# 8_PCIE-WIFI.net
KiCad netlist of a schematic drawn in Altium Designer
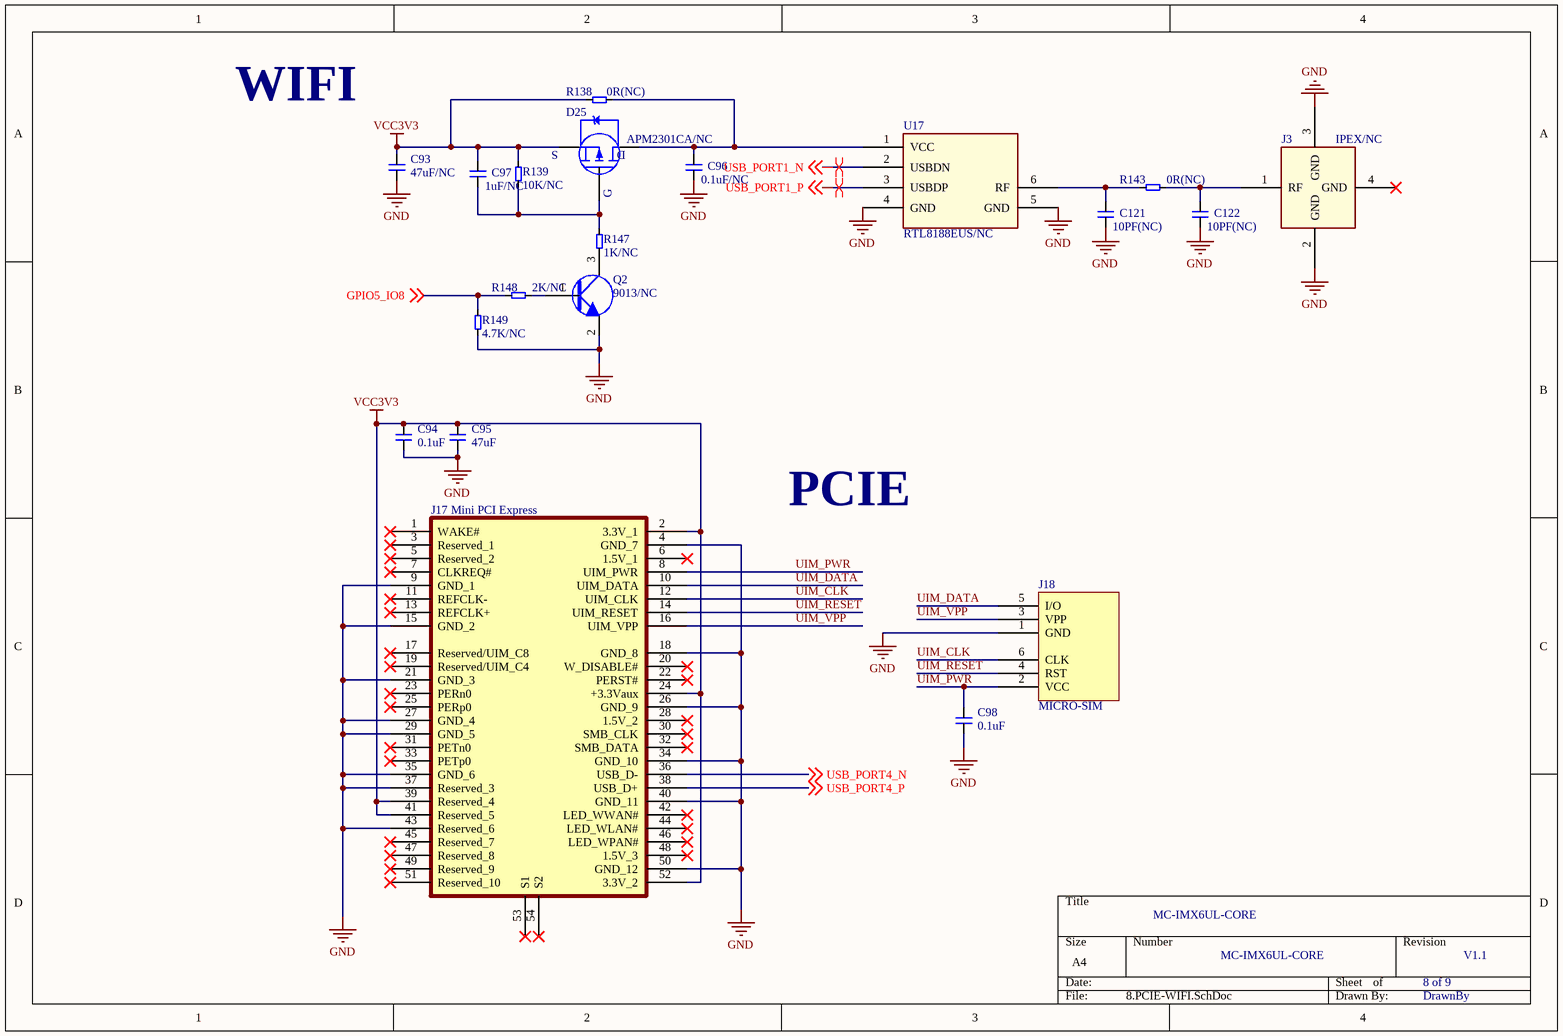
[diagram p0: 8.PCIE-WIFI.SchDoc]

(export (version "E")
  (design (tool "Eeschema 10.0.6"))
  (components
    (comp (ref "C93")
      (value "47uF/NC")
      (footprint "1206C")
      (description "电容")
      (libsource (lib "LDT-SCH") (part "电容"))
    )
    (comp (ref "C94")
      (value "0.1uF")
      (footprint "0603C")
      (description "电容")
      (libsource (lib "LDT-SCH") (part "电容"))
    )
    (comp (ref "C95")
      (value "47uF")
      (footprint "1206C")
      (description "电容")
      (libsource (lib "LDT-SCH") (part "电容"))
    )
    (comp (ref "C96")
      (value "0.1uF/NC")
      (footprint "0603C")
      (description "电容")
      (libsource (lib "LDT-SCH") (part "电容"))
    )
    (comp (ref "C97")
      (value "1uF/NC")
      (footprint "0603C")
      (description "电容")
      (libsource (lib "LDT-SCH") (part "电容"))
    )
    (comp (ref "C98")
      (value "0.1uF")
      (footprint "0603C")
      (description "电容")
      (libsource (lib "LDT-SCH") (part "电容"))
    )
    (comp (ref "C121")
      (value "10PF(NC)")
      (footprint "0402C")
      (description "电容")
      (libsource (lib "LDT-SCH") (part "电容"))
    )
    (comp (ref "C122")
      (value "10PF(NC)")
      (footprint "0402C")
      (description "电容")
      (libsource (lib "LDT-SCH") (part "电容"))
    )
    (comp (ref "D25")
      (value "APM2301CA/NC")
      (footprint "SOT-23")
      (libsource (lib "LDT-SCH") (part "APM2301CA"))
    )
    (comp (ref "J3") (value "IPEX/NC") (footprint "IPEX") (libsource (lib "LDT-SCH") (part "IPEX")))
    (comp (ref "J17")
      (value "Mini PCI Express")
      (footprint "MINI-PCIE")
      (description "MPC24-52K3311")
      (libsource (lib "LDT-SCH") (part "MINIPCIE"))
    )
    (comp (ref "J18")
      (value "MICRO-SIM")
      (footprint "MACRO-SIM")
      (libsource (lib "LDT-SCH") (part "MICRO-SIM"))
    )
    (comp (ref "Q2") (value "9013/NC") (footprint "SOT-23") (libsource (lib "LDT-SCH") (part "9013")))
    (comp (ref "R138")
      (value "0R(NC)")
      (footprint "0603R")
      (description "电阻")
      (libsource (lib "*") (part "电阻"))
    )
    (comp (ref "R139")
      (value "10K/NC")
      (footprint "0603R")
      (description "电阻")
      (libsource (lib "*") (part "电阻"))
    )
    (comp (ref "R143")
      (value "0R(NC)")
      (footprint "0402R")
      (description "电阻")
      (libsource (lib "*") (part "电阻"))
    )
    (comp (ref "R147")
      (value "1K/NC")
      (footprint "0603R")
      (description "电阻")
      (libsource (lib "*") (part "电阻"))
    )
    (comp (ref "R148")
      (value "2K/NC")
      (footprint "0603R")
      (description "电阻")
      (libsource (lib "*") (part "电阻"))
    )
    (comp (ref "R149")
      (value "4.7K/NC")
      (footprint "0603R")
      (description "电阻")
      (libsource (lib "*") (part "电阻"))
    )
    (comp (ref "U17")
      (value "RTL8188EUS/NC")
      (footprint "RTL8188EUS 13*12.2")
      (libsource (lib "LDT-SCH") (part "RTL8188EUS-13*12.2"))
    )
  )
  (nets
    (net (code "1") (name "/UIM_CLK") (class "Default")
      (node (ref "J17") (pin "12") (pinfunction "UIM_CLK_12") (pintype "passive"))
      (node (ref "J18") (pin "6") (pinfunction "CLK_6") (pintype "passive"))
    )
    (net (code "2") (name "/UIM_DATA") (class "Default")
      (node (ref "J17") (pin "10") (pinfunction "UIM_DATA_10") (pintype "passive"))
      (node (ref "J18") (pin "5") (pinfunction "I/O_5") (pintype "passive"))
    )
    (net (code "3") (name "/UIM_PWR") (class "Default")
      (node (ref "C98") (pin "1") (pintype "passive"))
      (node (ref "J17") (pin "8") (pinfunction "UIM_PWR_8") (pintype "passive"))
      (node (ref "J18") (pin "2") (pinfunction "VCC_2") (pintype "passive"))
    )
    (net (code "4") (name "/UIM_RESET") (class "Default")
      (node (ref "J17") (pin "14") (pinfunction "UIM_RESET_14") (pintype "passive"))
      (node (ref "J18") (pin "4") (pinfunction "RST_4") (pintype "passive"))
    )
    (net (code "5") (name "/UIM_VPP") (class "Default")
      (node (ref "J17") (pin "16") (pinfunction "UIM_VPP_16") (pintype "passive"))
      (node (ref "J18") (pin "3") (pinfunction "VPP_3") (pintype "passive"))
    )
    (net (code "6") (name "GND") (class "Default")
      (node (ref "C121") (pin "2") (pintype "passive"))
      (node (ref "C122") (pin "2") (pintype "passive"))
      (node (ref "C93") (pin "2") (pintype "passive"))
      (node (ref "C94") (pin "2") (pintype "passive"))
      (node (ref "C95") (pin "2") (pintype "passive"))
      (node (ref "C96") (pin "2") (pintype "passive"))
      (node (ref "C98") (pin "2") (pintype "passive"))
      (node (ref "J17") (pin "15") (pinfunction "GND_2_15") (pintype "passive"))
      (node (ref "J17") (pin "18") (pinfunction "GND_8_18") (pintype "passive"))
      (node (ref "J17") (pin "21") (pinfunction "GND_3_21") (pintype "passive"))
      (node (ref "J17") (pin "26") (pinfunction "GND_9_26") (pintype "passive"))
      (node (ref "J17") (pin "27") (pinfunction "GND_4_27") (pintype "passive"))
      (node (ref "J17") (pin "29") (pinfunction "GND_5_29") (pintype "passive"))
      (node (ref "J17") (pin "34") (pinfunction "GND_10_34") (pintype "passive"))
      (node (ref "J17") (pin "35") (pinfunction "GND_6_35") (pintype "passive"))
      (node (ref "J17") (pin "37") (pinfunction "Reserved_3_37") (pintype "passive"))
      (node (ref "J17") (pin "4") (pinfunction "GND_7_4") (pintype "passive"))
      (node (ref "J17") (pin "40") (pinfunction "GND_11_40") (pintype "passive"))
      (node (ref "J17") (pin "43") (pinfunction "Reserved_6_43") (pintype "passive"))
      (node (ref "J17") (pin "50") (pinfunction "GND_12_50") (pintype "passive"))
      (node (ref "J17") (pin "9") (pinfunction "GND_1_9") (pintype "passive"))
      (node (ref "J18") (pin "1") (pinfunction "GND_1") (pintype "passive"))
      (node (ref "J3") (pin "2") (pinfunction "GND_2") (pintype "passive"))
      (node (ref "J3") (pin "3") (pinfunction "GND_3") (pintype "passive"))
      (node (ref "Q2") (pin "2") (pintype "passive"))
      (node (ref "R149") (pin "2") (pintype "passive"))
      (node (ref "U17") (pin "4") (pinfunction "GND_4") (pintype "passive"))
      (node (ref "U17") (pin "5") (pinfunction "GND_5") (pintype "passive"))
    )
    (net (code "7") (name "GPIO5_IO8") (class "Default")
      (node (ref "R148") (pin "1") (pintype "passive"))
      (node (ref "R149") (pin "1") (pintype "passive"))
    )
    (net (code "8") (name "Net-(C97-Pad2)") (class "Default")
      (node (ref "C97") (pin "2") (pintype "passive"))
      (node (ref "D25") (pin "1") (pintype "passive"))
      (node (ref "R139") (pin "1") (pintype "passive"))
      (node (ref "R147") (pin "2") (pintype "passive"))
    )
    (net (code "9") (name "Net-(J3-RF)") (class "Default")
      (node (ref "C122") (pin "1") (pintype "passive"))
      (node (ref "J3") (pin "1") (pinfunction "RF_1") (pintype "passive"))
      (node (ref "R143") (pin "2") (pintype "passive"))
    )
    (net (code "10") (name "Net-(Q2-Pad1)") (class "Default")
      (node (ref "Q2") (pin "1") (pintype "passive"))
      (node (ref "R148") (pin "2") (pintype "passive"))
    )
    (net (code "11") (name "Net-(Q2-Pad3)") (class "Default")
      (node (ref "Q2") (pin "3") (pintype "passive"))
      (node (ref "R147") (pin "1") (pintype "passive"))
    )
    (net (code "12") (name "Net-(U17-RF)") (class "Default")
      (node (ref "C121") (pin "1") (pintype "passive"))
      (node (ref "R143") (pin "1") (pintype "passive"))
      (node (ref "U17") (pin "6") (pinfunction "RF_6") (pintype "passive"))
    )
    (net (code "13") (name "Net-(U17-VCC)") (class "Default")
      (node (ref "C96") (pin "1") (pintype "passive"))
      (node (ref "D25") (pin "3") (pintype "passive"))
      (node (ref "R138") (pin "1") (pintype "passive"))
      (node (ref "U17") (pin "1") (pinfunction "VCC_1") (pintype "passive"))
    )
    (net (code "14") (name "USB_PORT1_N") (class "Default")
      (node (ref "U17") (pin "2") (pinfunction "USBDN_2") (pintype "passive"))
    )
    (net (code "15") (name "USB_PORT1_P") (class "Default")
      (node (ref "U17") (pin "3") (pinfunction "USBDP_3") (pintype "passive"))
    )
    (net (code "16") (name "USB_PORT4_N") (class "Default")
      (node (ref "J17") (pin "36") (pinfunction "USB_D-_36") (pintype "passive"))
    )
    (net (code "17") (name "USB_PORT4_P") (class "Default")
      (node (ref "J17") (pin "38") (pinfunction "USB_D+_38") (pintype "passive"))
    )
    (net (code "18") (name "VCC3V3") (class "Default")
      (node (ref "C93") (pin "1") (pintype "passive"))
      (node (ref "C94") (pin "1") (pintype "passive"))
      (node (ref "C95") (pin "1") (pintype "passive"))
      (node (ref "C97") (pin "1") (pintype "passive"))
      (node (ref "D25") (pin "2") (pintype "passive"))
      (node (ref "J17") (pin "2") (pinfunction "3.3V_1_2") (pintype "passive"))
      (node (ref "J17") (pin "24") (pinfunction "+3.3Vaux_24") (pintype "passive"))
      (node (ref "J17") (pin "39") (pinfunction "Reserved_4_39") (pintype "passive"))
      (node (ref "J17") (pin "41") (pinfunction "Reserved_5_41") (pintype "passive"))
      (node (ref "J17") (pin "52") (pinfunction "3.3V_2_52") (pintype "passive"))
      (node (ref "R138") (pin "2") (pintype "passive"))
      (node (ref "R139") (pin "2") (pintype "passive"))
    )
    (net (code "19") (name "unconnected-(J3-GND-Pad4)") (class "Default")
      (node (ref "J3") (pin "4") (pinfunction "GND_4") (pintype "passive+no_connect"))
    )
    (net (code "20") (name "unconnected-(J17-1.5V_1-Pad6)") (class "Default")
      (node (ref "J17") (pin "6") (pinfunction "1.5V_1_6") (pintype "passive+no_connect"))
    )
    (net (code "21") (name "unconnected-(J17-1.5V_2-Pad28)") (class "Default")
      (node (ref "J17") (pin "28") (pinfunction "1.5V_2_28") (pintype "passive+no_connect"))
    )
    (net (code "22") (name "unconnected-(J17-1.5V_3-Pad48)") (class "Default")
      (node (ref "J17") (pin "48") (pinfunction "1.5V_3_48") (pintype "passive+no_connect"))
    )
    (net (code "23") (name "unconnected-(J17-CLKREQ#-Pad7)") (class "Default")
      (node (ref "J17") (pin "7") (pinfunction "CLKREQ#_7") (pintype "passive+no_connect"))
    )
    (net (code "24") (name "unconnected-(J17-LED_WLAN#-Pad44)") (class "Default")
      (node (ref "J17") (pin "44") (pinfunction "LED_WLAN#_44") (pintype "passive+no_connect"))
    )
    (net (code "25") (name "unconnected-(J17-LED_WPAN#-Pad46)") (class "Default")
      (node (ref "J17") (pin "46") (pinfunction "LED_WPAN#_46") (pintype "passive+no_connect"))
    )
    (net (code "26") (name "unconnected-(J17-LED_WWAN#-Pad42)") (class "Default")
      (node (ref "J17") (pin "42") (pinfunction "LED_WWAN#_42") (pintype "passive+no_connect"))
    )
    (net (code "27") (name "unconnected-(J17-PERST#-Pad22)") (class "Default")
      (node (ref "J17") (pin "22") (pinfunction "PERST#_22") (pintype "passive+no_connect"))
    )
    (net (code "28") (name "unconnected-(J17-PERn0-Pad23)") (class "Default")
      (node (ref "J17") (pin "23") (pinfunction "PERn0_23") (pintype "passive+no_connect"))
    )
    (net (code "29") (name "unconnected-(J17-PERp0-Pad25)") (class "Default")
      (node (ref "J17") (pin "25") (pinfunction "PERp0_25") (pintype "passive+no_connect"))
    )
    (net (code "30") (name "unconnected-(J17-PETn0-Pad31)") (class "Default")
      (node (ref "J17") (pin "31") (pinfunction "PETn0_31") (pintype "passive+no_connect"))
    )
    (net (code "31") (name "unconnected-(J17-PETp0-Pad33)") (class "Default")
      (node (ref "J17") (pin "33") (pinfunction "PETp0_33") (pintype "passive+no_connect"))
    )
    (net (code "32") (name "unconnected-(J17-REFCLK+-Pad13)") (class "Default")
      (node (ref "J17") (pin "13") (pinfunction "REFCLK+_13") (pintype "passive+no_connect"))
    )
    (net (code "33") (name "unconnected-(J17-REFCLK--Pad11)") (class "Default")
      (node (ref "J17") (pin "11") (pinfunction "REFCLK-_11") (pintype "passive+no_connect"))
    )
    (net (code "34") (name "unconnected-(J17-Reserved_1-Pad3)") (class "Default")
      (node (ref "J17") (pin "3") (pinfunction "Reserved_1_3") (pintype "passive+no_connect"))
    )
    (net (code "35") (name "unconnected-(J17-Reserved_2-Pad5)") (class "Default")
      (node (ref "J17") (pin "5") (pinfunction "Reserved_2_5") (pintype "passive+no_connect"))
    )
    (net (code "36") (name "unconnected-(J17-Reserved_7-Pad45)") (class "Default")
      (node (ref "J17") (pin "45") (pinfunction "Reserved_7_45") (pintype "passive+no_connect"))
    )
    (net (code "37") (name "unconnected-(J17-Reserved_8-Pad47)") (class "Default")
      (node (ref "J17") (pin "47") (pinfunction "Reserved_8_47") (pintype "passive+no_connect"))
    )
    (net (code "38") (name "unconnected-(J17-Reserved_9-Pad49)") (class "Default")
      (node (ref "J17") (pin "49") (pinfunction "Reserved_9_49") (pintype "passive+no_connect"))
    )
    (net (code "39") (name "unconnected-(J17-Reserved_10-Pad51)") (class "Default")
      (node (ref "J17") (pin "51") (pinfunction "Reserved_10_51") (pintype "passive+no_connect"))
    )
    (net (code "40") (name "unconnected-(J17-Reserved{slash}UIM_C4-Pad19)") (class "Default")
      (node (ref "J17") (pin "19") (pinfunction "Reserved/UIM_C4_19") (pintype "passive+no_connect"))
    )
    (net (code "41") (name "unconnected-(J17-Reserved{slash}UIM_C8-Pad17)") (class "Default")
      (node (ref "J17") (pin "17") (pinfunction "Reserved/UIM_C8_17") (pintype "passive+no_connect"))
    )
    (net (code "42") (name "unconnected-(J17-S1-Pad53)") (class "Default")
      (node (ref "J17") (pin "53") (pinfunction "S1_53") (pintype "passive+no_connect"))
    )
    (net (code "43") (name "unconnected-(J17-S2-Pad54)") (class "Default")
      (node (ref "J17") (pin "54") (pinfunction "S2_54") (pintype "passive+no_connect"))
    )
    (net (code "44") (name "unconnected-(J17-SMB_CLK-Pad30)") (class "Default")
      (node (ref "J17") (pin "30") (pinfunction "SMB_CLK_30") (pintype "passive+no_connect"))
    )
    (net (code "45") (name "unconnected-(J17-SMB_DATA-Pad32)") (class "Default")
      (node (ref "J17") (pin "32") (pinfunction "SMB_DATA_32") (pintype "passive+no_connect"))
    )
    (net (code "46") (name "unconnected-(J17-WAKE#-Pad1)") (class "Default")
      (node (ref "J17") (pin "1") (pinfunction "WAKE#_1") (pintype "passive+no_connect"))
    )
    (net (code "47") (name "unconnected-(J17-W_DISABLE#-Pad20)") (class "Default")
      (node (ref "J17") (pin "20") (pinfunction "W_DISABLE#_20") (pintype "passive+no_connect"))
    )
  )
)
